# Corn3.net
KiCad netlist of a schematic drawn in EAGLE
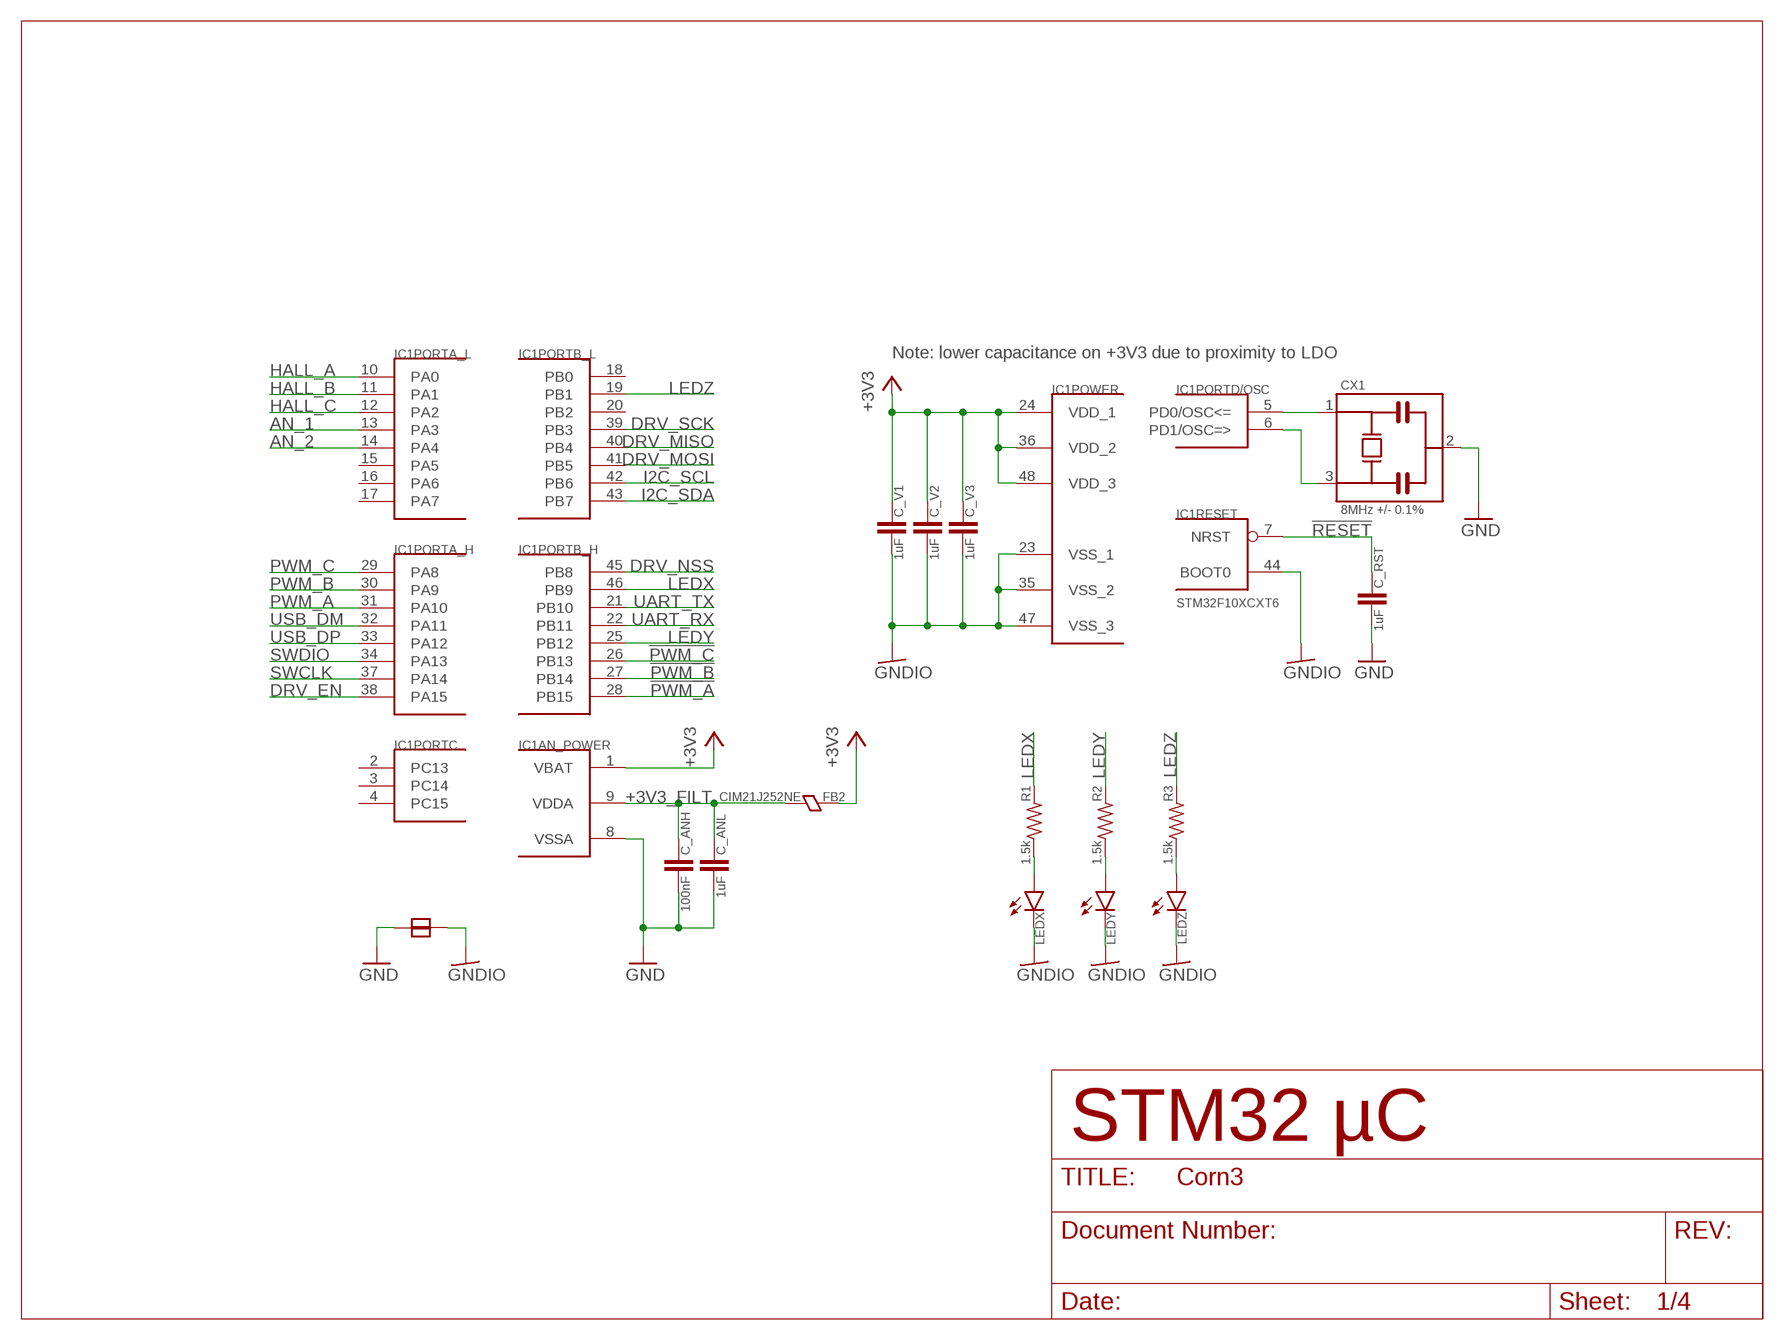
[diagram p0: schematic, sheet 1]
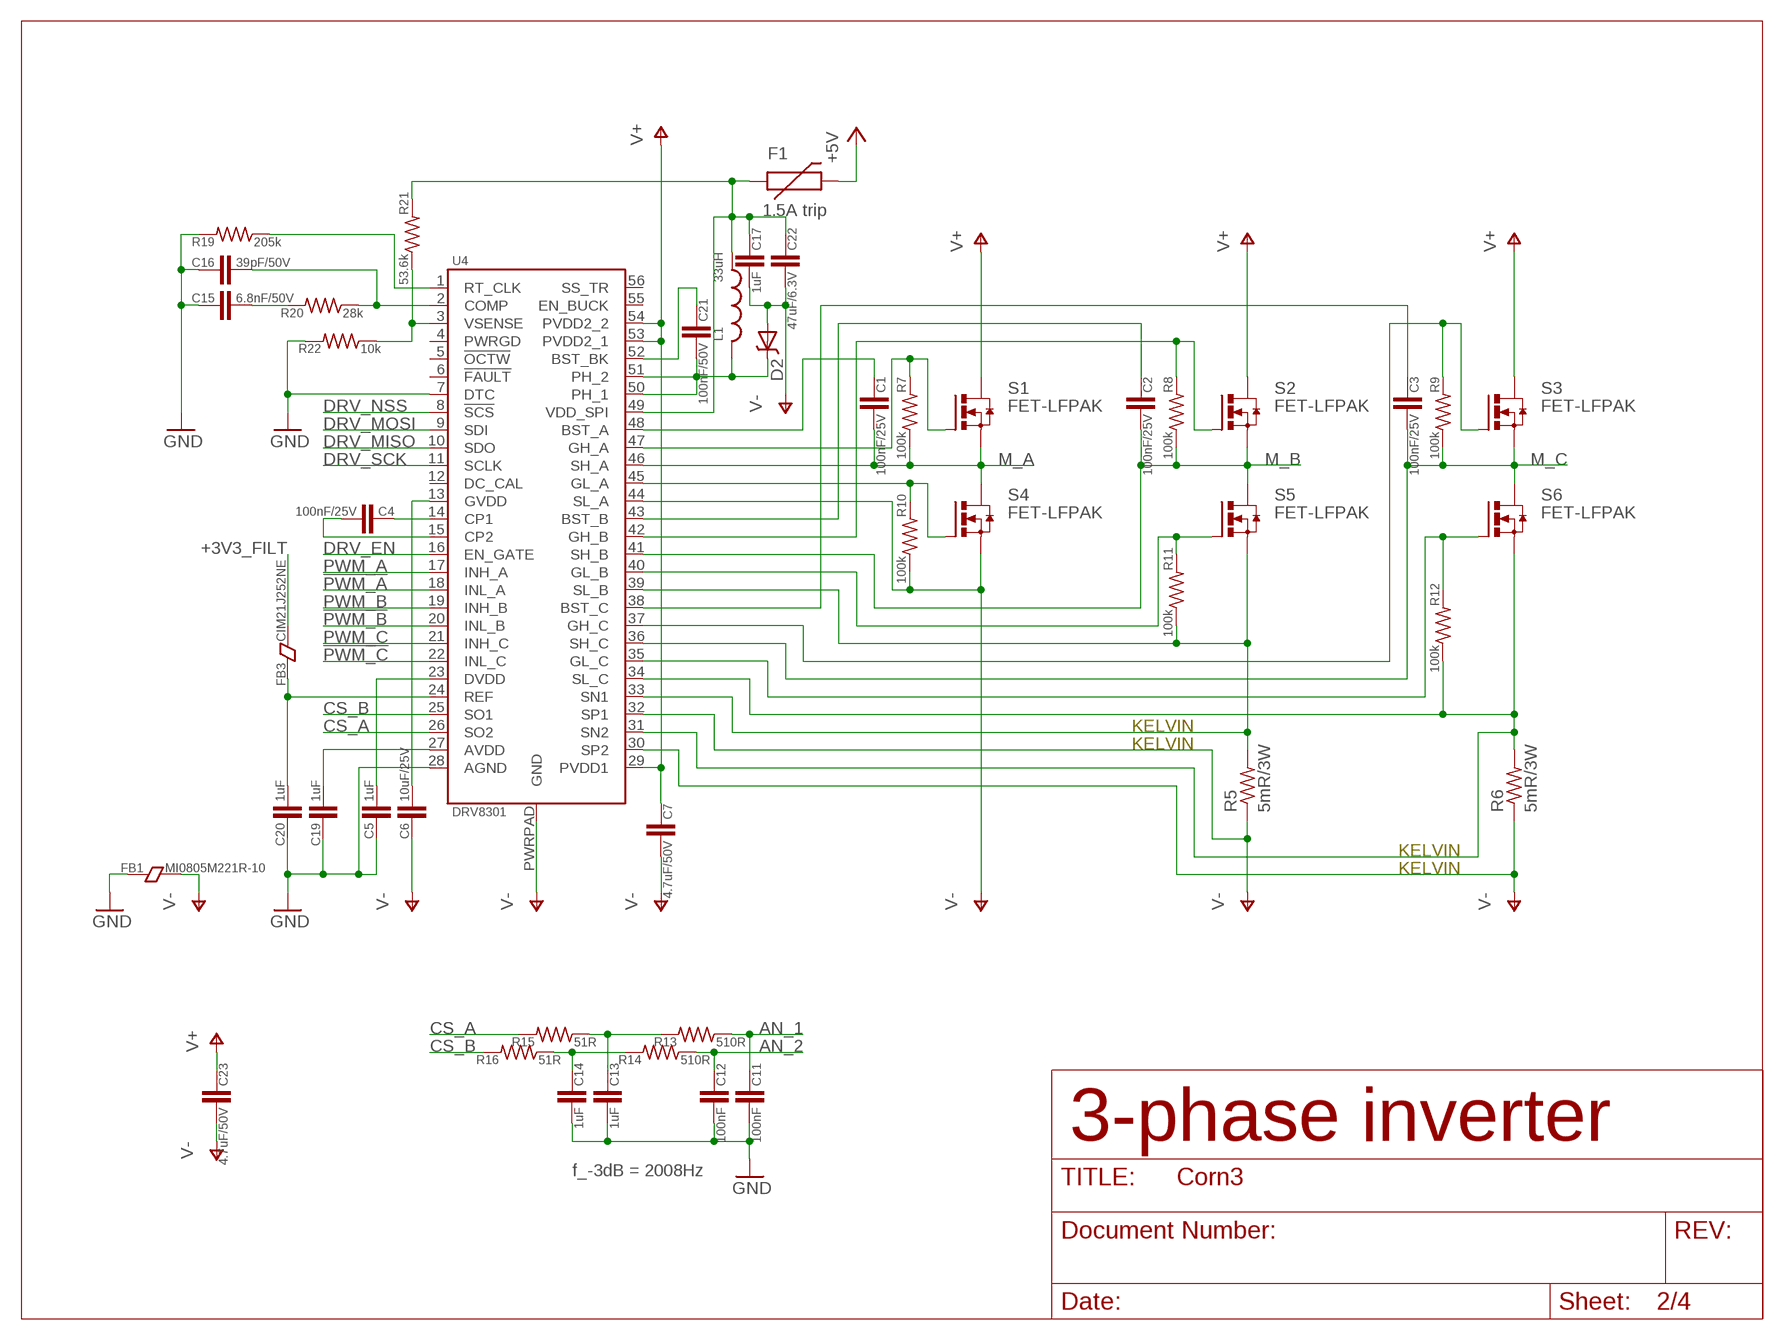
[diagram p1: schematic, sheet 2]
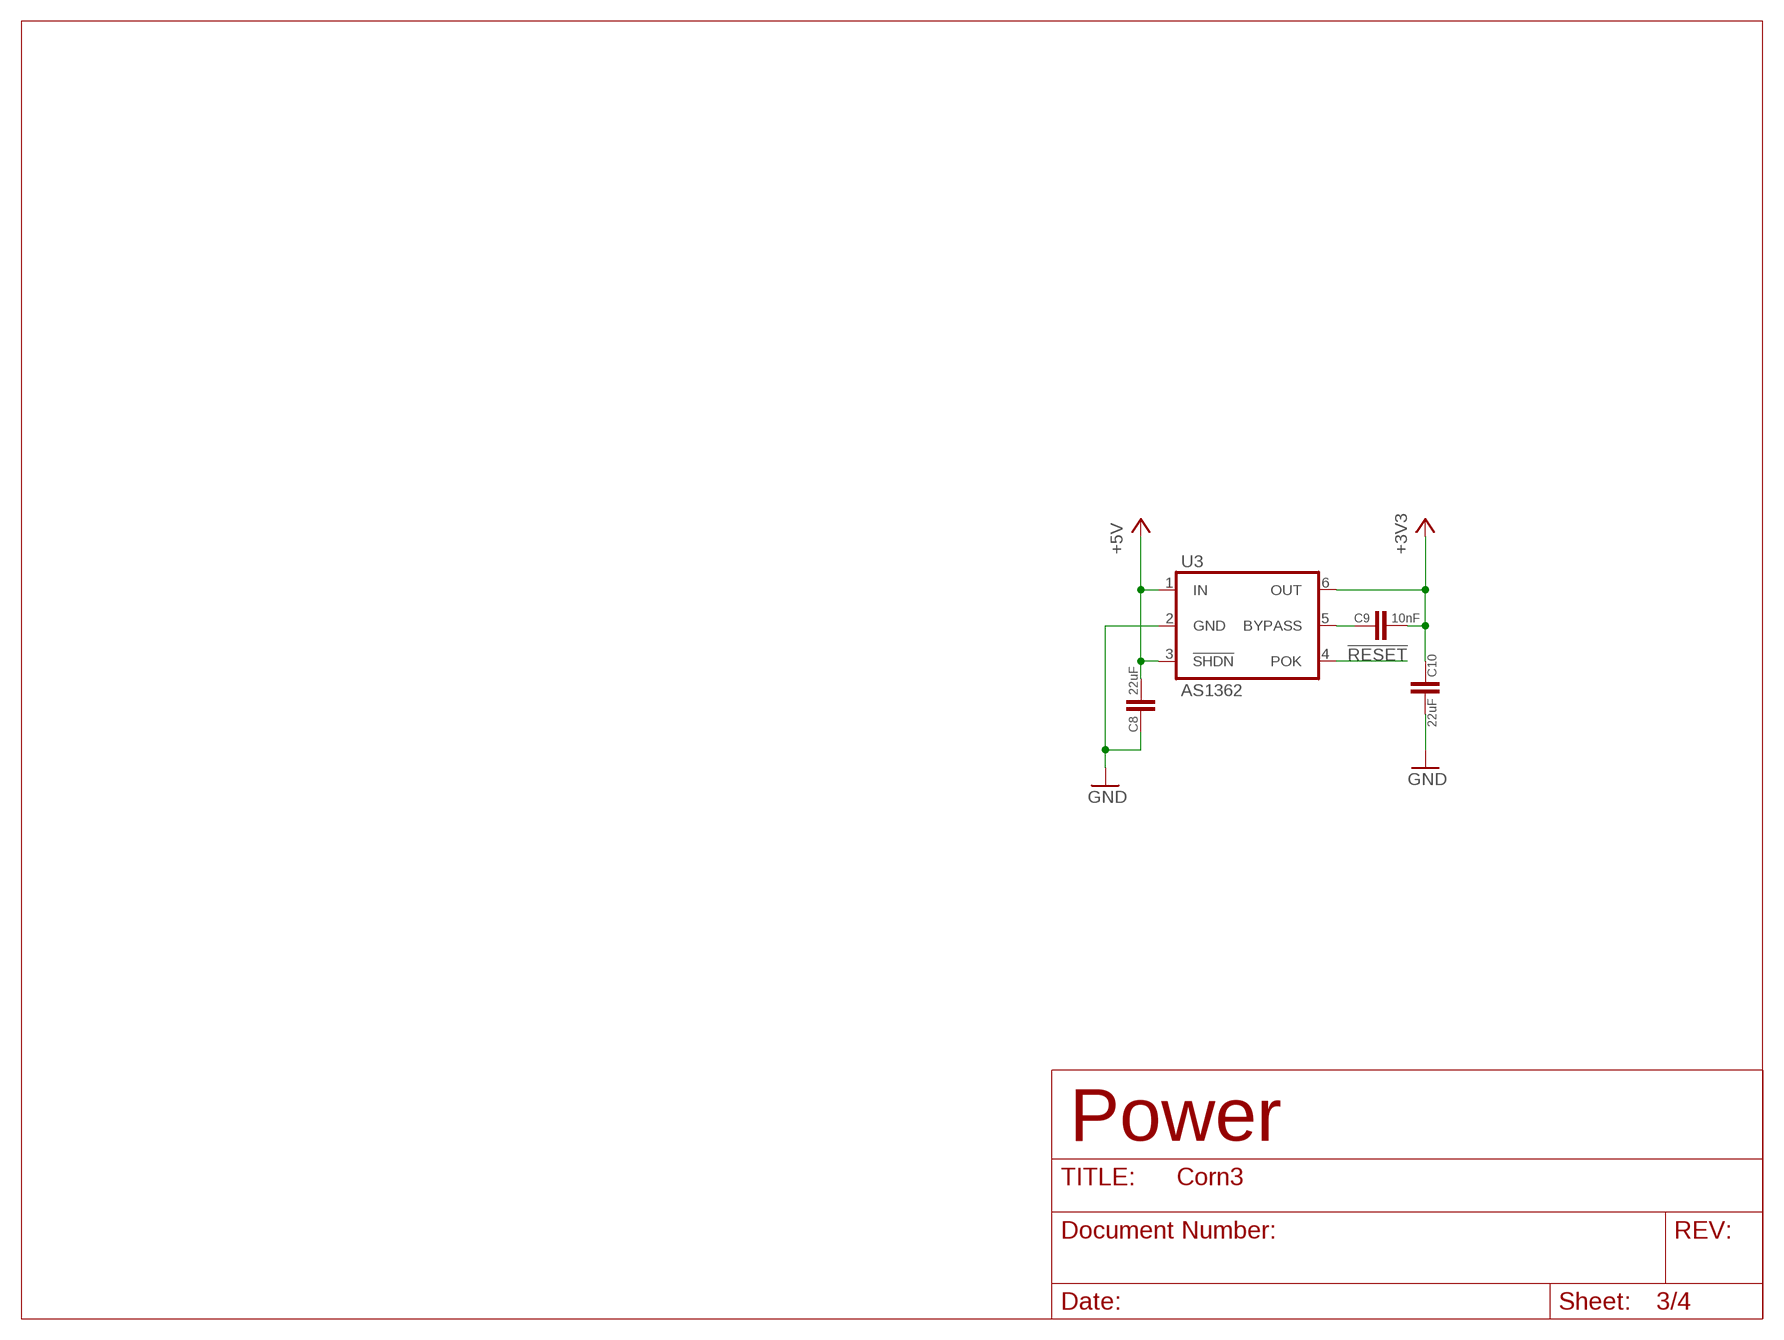
[diagram p2: schematic, sheet 3]
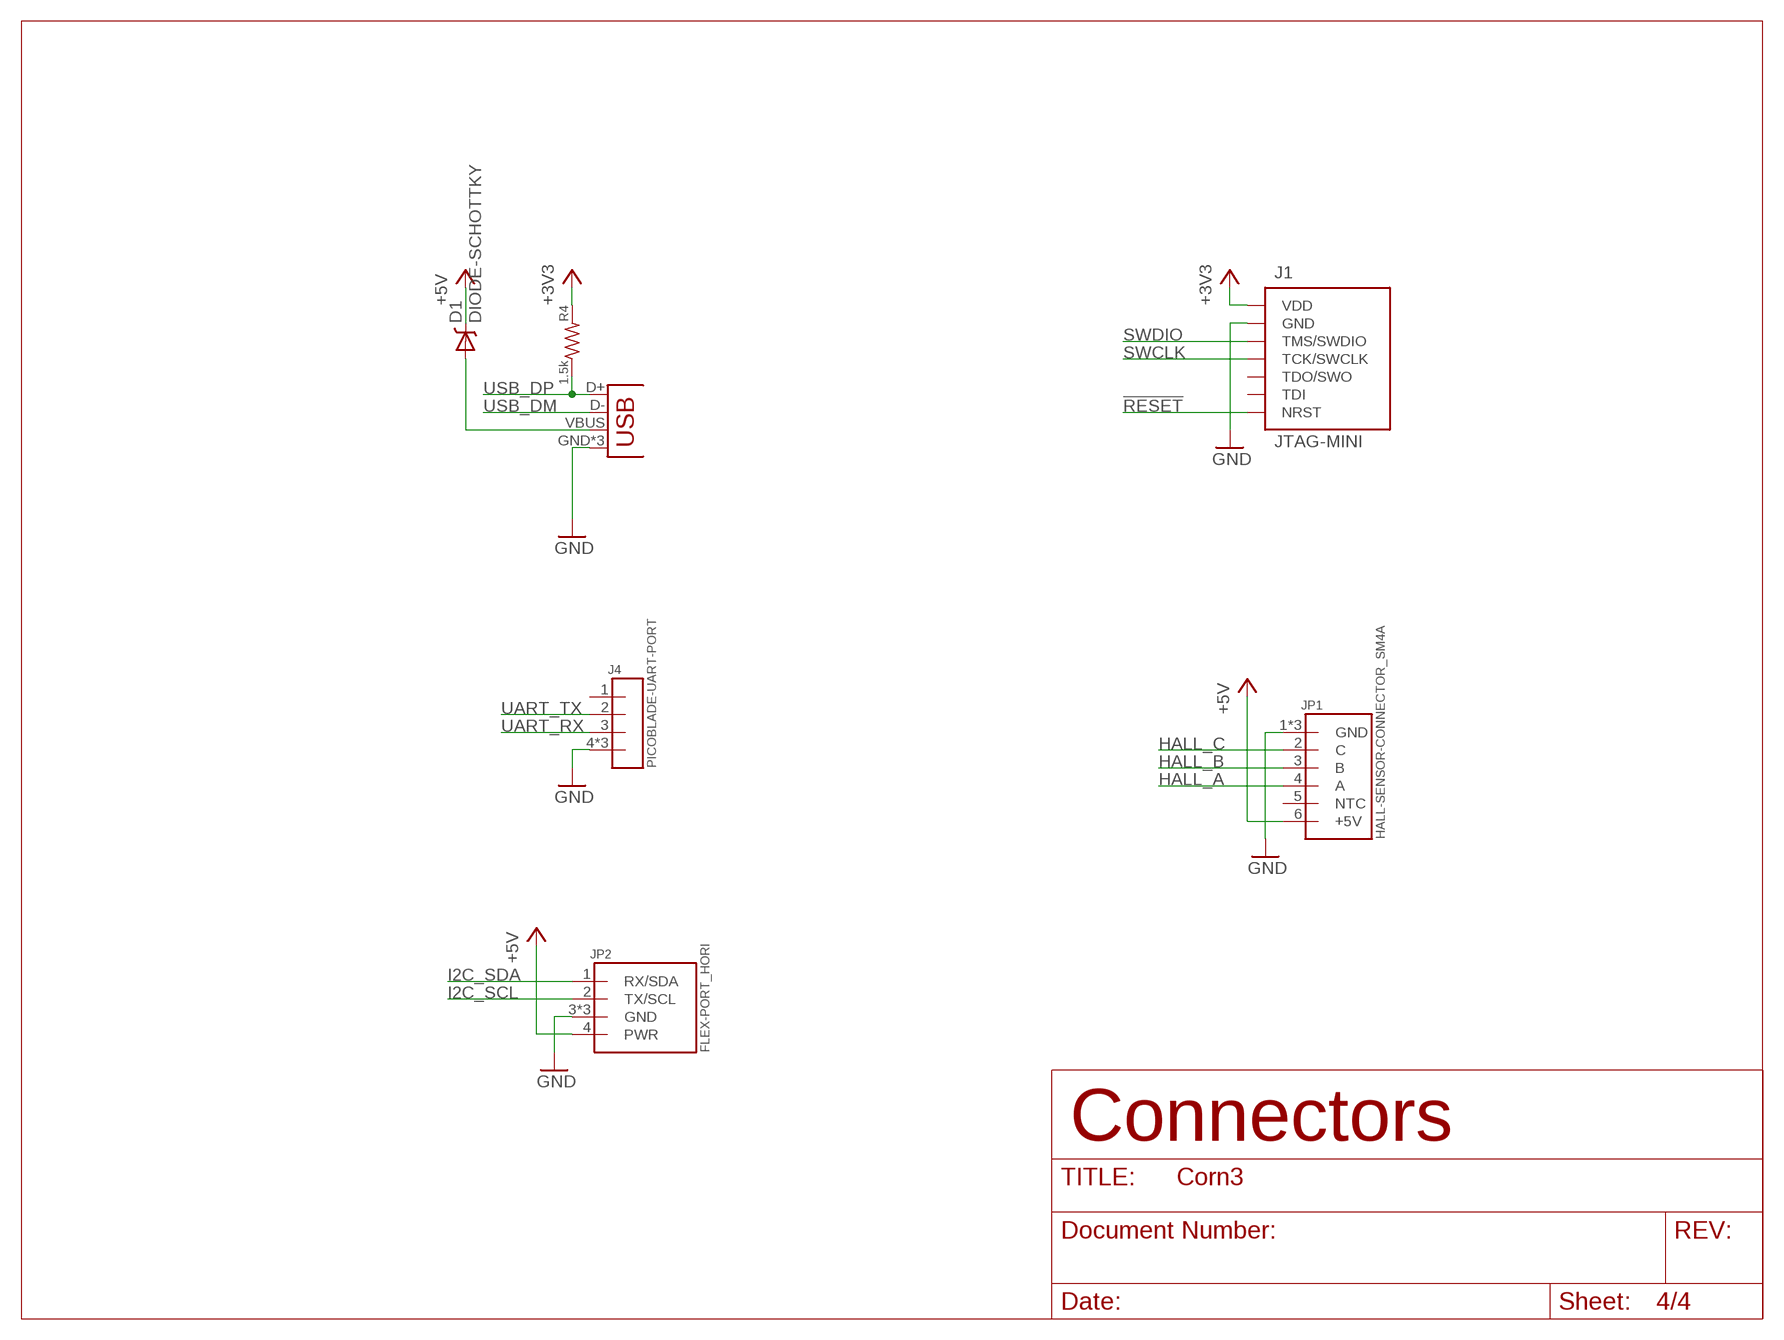
[diagram p3: schematic, sheet 4]

(export (version "E")
  (design (tool "Eeschema 10.0.6"))
  (components
    (comp (ref "C1")
      (value "100nF/25V")
      (footprint "eagle-import:0603")
      (libsource (lib "eagle-import") (part "C0603"))
    )
    (comp (ref "C2")
      (value "100nF/25V")
      (footprint "eagle-import:0603")
      (libsource (lib "eagle-import") (part "C0603"))
    )
    (comp (ref "C3")
      (value "100nF/25V")
      (footprint "eagle-import:0603")
      (libsource (lib "eagle-import") (part "C0603"))
    )
    (comp (ref "C4")
      (value "100nF/25V")
      (footprint "eagle-import:0603")
      (libsource (lib "eagle-import") (part "C0603"))
    )
    (comp (ref "C5")
      (value "1uF")
      (footprint "eagle-import:0603")
      (libsource (lib "eagle-import") (part "C0603"))
    )
    (comp (ref "C6")
      (value "10uF/25V")
      (footprint "eagle-import:0805")
      (libsource (lib "eagle-import") (part "C0805"))
    )
    (comp (ref "C7")
      (value "4.7uF/50V")
      (footprint "eagle-import:1206")
      (libsource (lib "eagle-import") (part "C1206"))
    )
    (comp (ref "C11")
      (value "100nF")
      (footprint "eagle-import:0603")
      (libsource (lib "eagle-import") (part "C0603"))
    )
    (comp (ref "C12")
      (value "100nF")
      (footprint "eagle-import:0603")
      (libsource (lib "eagle-import") (part "C0603"))
    )
    (comp (ref "C13")
      (value "1uF")
      (footprint "eagle-import:0603")
      (libsource (lib "eagle-import") (part "C0603"))
    )
    (comp (ref "C14")
      (value "1uF")
      (footprint "eagle-import:0603")
      (libsource (lib "eagle-import") (part "C0603"))
    )
    (comp (ref "C15")
      (value "6.8nF/50V")
      (footprint "eagle-import:0603")
      (libsource (lib "eagle-import") (part "C0603"))
    )
    (comp (ref "C16")
      (value "39pF/50V")
      (footprint "eagle-import:0603")
      (libsource (lib "eagle-import") (part "C0603"))
    )
    (comp (ref "C17")
      (value "1uF")
      (footprint "eagle-import:0603")
      (libsource (lib "eagle-import") (part "C0603"))
    )
    (comp (ref "C19")
      (value "1uF")
      (footprint "eagle-import:0603")
      (libsource (lib "eagle-import") (part "C0603"))
    )
    (comp (ref "C20")
      (value "1uF")
      (footprint "eagle-import:0603")
      (libsource (lib "eagle-import") (part "C0603"))
    )
    (comp (ref "C21")
      (value "100nF/50V")
      (footprint "eagle-import:0603")
      (libsource (lib "eagle-import") (part "C0603"))
    )
    (comp (ref "C22")
      (value "47uF/6.3V")
      (footprint "eagle-import:0805")
      (libsource (lib "eagle-import") (part "C0805"))
    )
    (comp (ref "C23")
      (value "4.7uF/50V")
      (footprint "eagle-import:1206")
      (libsource (lib "eagle-import") (part "C1206"))
    )
    (comp (ref "D2")
      (value "DIODE-SCHOTTKY_")
      (footprint "eagle-import:SMA-DIODE")
      (libsource (lib "eagle-import") (part "DIODE-SCHOTTKY_"))
    )
    (comp (ref "F1")
      (value "1.5A trip")
      (footprint "eagle-import:PTC-1206")
      (libsource (lib "eagle-import") (part "PTCSMD"))
    )
    (comp (ref "FB1")
      (value "MI0805M221R-10")
      (footprint "eagle-import:0805")
      (libsource (lib "eagle-import") (part "FERRITE0805"))
    )
    (comp (ref "FB3")
      (value "CIM21J252NE")
      (footprint "eagle-import:0805")
      (libsource (lib "eagle-import") (part "FERRITE0805"))
    )
    (comp (ref "L1")
      (value "33uH")
      (footprint "eagle-import:TAIYO-YUDEN_NR40")
      (libsource (lib "eagle-import") (part "L-US_NR40"))
    )
    (comp (ref "R5")
      (value "5mR/3W")
      (footprint "eagle-import:R2512")
      (libsource (lib "eagle-import") (part "R-US_R2512"))
    )
    (comp (ref "R6")
      (value "5mR/3W")
      (footprint "eagle-import:R2512")
      (libsource (lib "eagle-import") (part "R-US_R2512"))
    )
    (comp (ref "R7")
      (value "100k")
      (footprint "eagle-import:0603")
      (libsource (lib "eagle-import") (part "R0603"))
    )
    (comp (ref "R8")
      (value "100k")
      (footprint "eagle-import:0603")
      (libsource (lib "eagle-import") (part "R0603"))
    )
    (comp (ref "R9")
      (value "100k")
      (footprint "eagle-import:0603")
      (libsource (lib "eagle-import") (part "R0603"))
    )
    (comp (ref "R10")
      (value "100k")
      (footprint "eagle-import:0603")
      (libsource (lib "eagle-import") (part "R0603"))
    )
    (comp (ref "R11")
      (value "100k")
      (footprint "eagle-import:0603")
      (libsource (lib "eagle-import") (part "R0603"))
    )
    (comp (ref "R12")
      (value "100k")
      (footprint "eagle-import:0603")
      (libsource (lib "eagle-import") (part "R0603"))
    )
    (comp (ref "R13")
      (value "510R")
      (footprint "eagle-import:0603")
      (libsource (lib "eagle-import") (part "R0603"))
    )
    (comp (ref "R14")
      (value "510R")
      (footprint "eagle-import:0603")
      (libsource (lib "eagle-import") (part "R0603"))
    )
    (comp (ref "R15")
      (value "51R")
      (footprint "eagle-import:0603")
      (libsource (lib "eagle-import") (part "R0603"))
    )
    (comp (ref "R16")
      (value "51R")
      (footprint "eagle-import:0603")
      (libsource (lib "eagle-import") (part "R0603"))
    )
    (comp (ref "R19")
      (value "205k")
      (footprint "eagle-import:0603")
      (libsource (lib "eagle-import") (part "R0603"))
    )
    (comp (ref "R20")
      (value "28k")
      (footprint "eagle-import:0603")
      (libsource (lib "eagle-import") (part "R0603"))
    )
    (comp (ref "R21")
      (value "53.6k")
      (footprint "eagle-import:0603")
      (libsource (lib "eagle-import") (part "R0603"))
    )
    (comp (ref "R22")
      (value "10k")
      (footprint "eagle-import:0603")
      (libsource (lib "eagle-import") (part "R0603"))
    )
    (comp (ref "S1")
      (value "FET-LFPAK")
      (footprint "eagle-import:SON-5X6")
      (libsource (lib "eagle-import") (part "MOSFET-N56"))
    )
    (comp (ref "S2")
      (value "FET-LFPAK")
      (footprint "eagle-import:SON-5X6")
      (libsource (lib "eagle-import") (part "MOSFET-N56"))
    )
    (comp (ref "S3")
      (value "FET-LFPAK")
      (footprint "eagle-import:SON-5X6")
      (libsource (lib "eagle-import") (part "MOSFET-N56"))
    )
    (comp (ref "S4")
      (value "FET-LFPAK")
      (footprint "eagle-import:SON-5X6")
      (libsource (lib "eagle-import") (part "MOSFET-N56"))
    )
    (comp (ref "S5")
      (value "FET-LFPAK")
      (footprint "eagle-import:SON-5X6")
      (libsource (lib "eagle-import") (part "MOSFET-N56"))
    )
    (comp (ref "S6")
      (value "FET-LFPAK")
      (footprint "eagle-import:SON-5X6")
      (libsource (lib "eagle-import") (part "MOSFET-N56"))
    )
    (comp (ref "U4")
      (value "DRV8301")
      (footprint "eagle-import:HTSSOP-56")
      (libsource (lib "eagle-import") (part "DRV8301"))
    )
    (comp (ref "C8")
      (value "22uF")
      (footprint "eagle-import:0805")
      (libsource (lib "eagle-import") (part "C0805"))
    )
    (comp (ref "C9")
      (value "10nF")
      (footprint "eagle-import:0603")
      (libsource (lib "eagle-import") (part "C0603"))
    )
    (comp (ref "C10")
      (value "22uF")
      (footprint "eagle-import:0805")
      (libsource (lib "eagle-import") (part "C0805"))
    )
    (comp (ref "U3")
      (value "AS1362")
      (footprint "eagle-import:SOT23-6")
      (libsource (lib "eagle-import") (part "AS1362"))
    )
    (comp (ref "D1")
      (value "DIODE-SCHOTTKY")
      (footprint "eagle-import:SOD-523")
      (libsource (lib "eagle-import") (part "DIODE-SCHOTTKY"))
    )
    (comp (ref "J1")
      (value "JTAG-MINI")
      (footprint "eagle-import:JTAG-MINI")
      (libsource (lib "eagle-import") (part "JTAG-MINI"))
    )
    (comp (ref "J4")
      (value "PICOBLADE-UART-PORT")
      (footprint "eagle-import:PICOBLADE-04-SMD-RA")
      (libsource (lib "eagle-import") (part "PICOBLADE-UART-PORT"))
    )
    (comp (ref "JP1")
      (value "HALL-SENSOR-CONNECTOR_SM4A")
      (footprint "eagle-import:JST_S6B-ZR-SM4A")
      (libsource (lib "eagle-import") (part "HALL-SENSOR-CONNECTOR_SM4A"))
    )
    (comp (ref "JP2")
      (value "FLEX-PORT_HORI")
      (footprint "eagle-import:JST_SM04B-SRSS")
      (libsource (lib "eagle-import") (part "FLEX-PORT_HORI"))
    )
    (comp (ref "JP3")
      (value "USB-MICROB")
      (footprint "eagle-import:USB-MICROB")
      (libsource (lib "eagle-import") (part "USB-MICROB"))
    )
    (comp (ref "R4")
      (value "1.5k")
      (footprint "eagle-import:0603")
      (libsource (lib "eagle-import") (part "R0603"))
    )
    (comp (ref "CX1")
      (value "8MHz +/- 0.1%")
      (footprint "eagle-import:MURATA_CSTCE")
      (libsource (lib "eagle-import") (part "MURATA_CSTCE"))
    )
    (comp (ref "C_ANH")
      (value "100nF")
      (footprint "eagle-import:0603")
      (libsource (lib "eagle-import") (part "C0603"))
    )
    (comp (ref "C_ANL")
      (value "1uF")
      (footprint "eagle-import:0603")
      (libsource (lib "eagle-import") (part "C0603"))
    )
    (comp (ref "C_RST")
      (value "1uF")
      (footprint "eagle-import:0603")
      (libsource (lib "eagle-import") (part "C0603"))
    )
    (comp (ref "C_V1")
      (value "1uF")
      (footprint "eagle-import:0603")
      (libsource (lib "eagle-import") (part "C0603"))
    )
    (comp (ref "C_V2")
      (value "1uF")
      (footprint "eagle-import:0603")
      (libsource (lib "eagle-import") (part "C0603"))
    )
    (comp (ref "C_V3")
      (value "1uF")
      (footprint "eagle-import:0603")
      (libsource (lib "eagle-import") (part "C0603"))
    )
    (comp (ref "FB2")
      (value "CIM21J252NE")
      (footprint "eagle-import:0805")
      (libsource (lib "eagle-import") (part "FERRITE0805"))
    )
    (comp (ref "IC1")
      (value "STM32F10XCXT6")
      (footprint "eagle-import:TQFP48")
      (libsource (lib "eagle-import") (part "STM32F10XCXT6"))
    )
    (comp (ref "JUMPER-GND-GNDIO")
      (value "JUMPER5025")
      (footprint "eagle-import:5025")
      (libsource (lib "eagle-import") (part "JUMPER5025"))
    )
    (comp (ref "LEDX")
      (value "LED0805")
      (footprint "eagle-import:0805_POL")
      (libsource (lib "eagle-import") (part "LED0805"))
    )
    (comp (ref "LEDY")
      (value "LED0805")
      (footprint "eagle-import:0805_POL")
      (libsource (lib "eagle-import") (part "LED0805"))
    )
    (comp (ref "LEDZ")
      (value "LED0805")
      (footprint "eagle-import:0805_POL")
      (libsource (lib "eagle-import") (part "LED0805"))
    )
    (comp (ref "R1")
      (value "1.5k")
      (footprint "eagle-import:0603")
      (libsource (lib "eagle-import") (part "R0603"))
    )
    (comp (ref "R2")
      (value "1.5k")
      (footprint "eagle-import:0603")
      (libsource (lib "eagle-import") (part "R0603"))
    )
    (comp (ref "R3")
      (value "1.5k")
      (footprint "eagle-import:0603")
      (libsource (lib "eagle-import") (part "R0603"))
    )
  )
  (nets
    (net (code "1") (name "+3V3") (class "Default")
      (node (ref "C10") (pin "1") (pinfunction "1_1") (pintype "passive"))
      (node (ref "C9") (pin "2") (pinfunction "2_2") (pintype "passive"))
      (node (ref "C_V1") (pin "1") (pinfunction "1_1") (pintype "passive"))
      (node (ref "C_V2") (pin "1") (pinfunction "1_1") (pintype "passive"))
      (node (ref "C_V3") (pin "1") (pinfunction "1_1") (pintype "passive"))
      (node (ref "FB2") (pin "2") (pinfunction "2_2") (pintype "passive"))
      (node (ref "IC1") (pin "1") (pinfunction "VBAT_1") (pintype "power_in"))
      (node (ref "IC1") (pin "24") (pinfunction "VDD_1_24") (pintype "power_in"))
      (node (ref "IC1") (pin "36") (pinfunction "VDD_2_36") (pintype "power_in"))
      (node (ref "IC1") (pin "48") (pinfunction "VDD_3_48") (pintype "power_in"))
      (node (ref "J1") (pin "VDD") (pinfunction "VDD_VDD") (pintype "bidirectional"))
      (node (ref "R4") (pin "2") (pinfunction "2_2") (pintype "passive"))
      (node (ref "U3") (pin "6") (pinfunction "OUT_6") (pintype "power_in"))
    )
    (net (code "2") (name "+3V3_FILT") (class "Default")
      (node (ref "C_ANH") (pin "1") (pinfunction "1_1") (pintype "passive"))
      (node (ref "C_ANL") (pin "1") (pinfunction "1_1") (pintype "passive"))
      (node (ref "FB2") (pin "1") (pinfunction "1_1") (pintype "passive"))
      (node (ref "FB3") (pin "1") (pinfunction "1_1") (pintype "passive"))
      (node (ref "IC1") (pin "9") (pinfunction "VDDA_9") (pintype "power_in"))
    )
    (net (code "3") (name "+5V") (class "Default")
      (node (ref "C8") (pin "2") (pinfunction "2_2") (pintype "passive"))
      (node (ref "D1") (pin "C") (pinfunction "C_C") (pintype "passive"))
      (node (ref "F1") (pin "2") (pinfunction "2_2") (pintype "bidirectional"))
      (node (ref "JP1") (pin "6") (pinfunction "+5V_6") (pintype "bidirectional"))
      (node (ref "JP2") (pin "4") (pinfunction "PWR_4") (pintype "bidirectional"))
      (node (ref "U3") (pin "1") (pinfunction "IN_1") (pintype "power_in"))
      (node (ref "U3") (pin "3") (pinfunction "~{SHDN}_3") (pintype "input"))
    )
    (net (code "4") (name "AN_1") (class "Default")
      (node (ref "C11") (pin "1") (pinfunction "1_1") (pintype "passive"))
      (node (ref "IC1") (pin "13") (pinfunction "PA3_13") (pintype "bidirectional"))
      (node (ref "R13") (pin "1") (pinfunction "1_1") (pintype "passive"))
    )
    (net (code "5") (name "AN_2") (class "Default")
      (node (ref "C12") (pin "1") (pinfunction "1_1") (pintype "passive"))
      (node (ref "IC1") (pin "14") (pinfunction "PA4_14") (pintype "bidirectional"))
      (node (ref "R14") (pin "1") (pinfunction "1_1") (pintype "passive"))
    )
    (net (code "6") (name "CS_A") (class "Default")
      (node (ref "R15") (pin "2") (pinfunction "2_2") (pintype "passive"))
      (node (ref "U4") (pin "26") (pinfunction "SO2_26") (pintype "output"))
    )
    (net (code "7") (name "CS_B") (class "Default")
      (node (ref "R16") (pin "2") (pinfunction "2_2") (pintype "passive"))
      (node (ref "U4") (pin "25") (pinfunction "SO1_25") (pintype "output"))
    )
    (net (code "8") (name "DRV_EN") (class "Default")
      (node (ref "IC1") (pin "38") (pinfunction "PA15_38") (pintype "bidirectional"))
      (node (ref "U4") (pin "16") (pinfunction "EN_GATE_16") (pintype "input"))
    )
    (net (code "9") (name "DRV_MISO") (class "Default")
      (node (ref "IC1") (pin "40") (pinfunction "PB4_40") (pintype "bidirectional"))
      (node (ref "U4") (pin "10") (pinfunction "SDO_10") (pintype "output"))
    )
    (net (code "10") (name "DRV_MOSI") (class "Default")
      (node (ref "IC1") (pin "41") (pinfunction "PB5_41") (pintype "bidirectional"))
      (node (ref "U4") (pin "9") (pinfunction "SDI_9") (pintype "input"))
    )
    (net (code "11") (name "DRV_NSS") (class "Default")
      (node (ref "IC1") (pin "45") (pinfunction "PB8_45") (pintype "bidirectional"))
      (node (ref "U4") (pin "8") (pinfunction "~{SCS}_8") (pintype "input"))
    )
    (net (code "12") (name "DRV_SCK") (class "Default")
      (node (ref "IC1") (pin "39") (pinfunction "PB3_39") (pintype "bidirectional"))
      (node (ref "U4") (pin "11") (pinfunction "SCLK_11") (pintype "input"))
    )
    (net (code "13") (name "GND") (class "Default")
      (node (ref "C10") (pin "2") (pinfunction "2_2") (pintype "passive"))
      (node (ref "C11") (pin "2") (pinfunction "2_2") (pintype "passive"))
      (node (ref "C12") (pin "2") (pinfunction "2_2") (pintype "passive"))
      (node (ref "C13") (pin "2") (pinfunction "2_2") (pintype "passive"))
      (node (ref "C14") (pin "2") (pinfunction "2_2") (pintype "passive"))
      (node (ref "C15") (pin "1") (pinfunction "1_1") (pintype "passive"))
      (node (ref "C16") (pin "1") (pinfunction "1_1") (pintype "passive"))
      (node (ref "C19") (pin "1") (pinfunction "1_1") (pintype "passive"))
      (node (ref "C20") (pin "1") (pinfunction "1_1") (pintype "passive"))
      (node (ref "C5") (pin "1") (pinfunction "1_1") (pintype "passive"))
      (node (ref "C8") (pin "1") (pinfunction "1_1") (pintype "passive"))
      (node (ref "CX1") (pin "2") (pinfunction "P$2_2") (pintype "bidirectional"))
      (node (ref "C_ANH") (pin "2") (pinfunction "2_2") (pintype "passive"))
      (node (ref "C_ANL") (pin "2") (pinfunction "2_2") (pintype "passive"))
      (node (ref "C_RST") (pin "2") (pinfunction "2_2") (pintype "passive"))
      (node (ref "FB1") (pin "2") (pinfunction "2_2") (pintype "passive"))
      (node (ref "IC1") (pin "8") (pinfunction "VSSA_8") (pintype "power_in"))
      (node (ref "J1") (pin "GND1") (pinfunction "GND_GND1") (pintype "bidirectional"))
      (node (ref "J1") (pin "GND2") (pinfunction "GND_GND2") (pintype "bidirectional"))
      (node (ref "J1") (pin "GND3") (pinfunction "GND_GND3") (pintype "bidirectional"))
      (node (ref "J1") (pin "GND4") (pinfunction "GND_GND4") (pintype "bidirectional"))
      (node (ref "J4") (pin "4") (pinfunction "4_4") (pintype "bidirectional"))
      (node (ref "J4") (pin "TAB1") (pinfunction "4_TAB1") (pintype "bidirectional"))
      (node (ref "J4") (pin "TAB2") (pinfunction "4_TAB2") (pintype "bidirectional"))
      (node (ref "JP1") (pin "1") (pinfunction "GND_1") (pintype "bidirectional"))
      (node (ref "JP1") (pin "TAB1") (pinfunction "GND_TAB1") (pintype "bidirectional"))
      (node (ref "JP1") (pin "TAB2") (pinfunction "GND_TAB2") (pintype "bidirectional"))
      (node (ref "JP2") (pin "3") (pinfunction "GND_3") (pintype "bidirectional"))
      (node (ref "JP2") (pin "TAB1") (pinfunction "GND_TAB1") (pintype "bidirectional"))
      (node (ref "JP2") (pin "TAB2") (pinfunction "GND_TAB2") (pintype "bidirectional"))
      (node (ref "JP3") (pin "GND") (pinfunction "GND_GND") (pintype "bidirectional"))
      (node (ref "JP3") (pin "MT1") (pinfunction "GND_MT1") (pintype "bidirectional"))
      (node (ref "JP3") (pin "MT2") (pinfunction "GND_MT2") (pintype "bidirectional"))
      (node (ref "JUMPER-GND-GNDIO") (pin "1") (pinfunction "1_1") (pintype "bidirectional"))
      (node (ref "R19") (pin "2") (pinfunction "2_2") (pintype "passive"))
      (node (ref "R22") (pin "2") (pinfunction "2_2") (pintype "passive"))
      (node (ref "U3") (pin "2") (pinfunction "GND_2") (pintype "power_in"))
      (node (ref "U4") (pin "28") (pinfunction "AGND_28") (pintype "power_in"))
      (node (ref "U4") (pin "7") (pinfunction "DTC_7") (pintype "input"))
    )
    (net (code "14") (name "GNDIO") (class "Default")
      (node (ref "C_V1") (pin "2") (pinfunction "2_2") (pintype "passive"))
      (node (ref "C_V2") (pin "2") (pinfunction "2_2") (pintype "passive"))
      (node (ref "C_V3") (pin "2") (pinfunction "2_2") (pintype "passive"))
      (node (ref "IC1") (pin "23") (pinfunction "VSS_1_23") (pintype "power_in"))
      (node (ref "IC1") (pin "35") (pinfunction "VSS_2_35") (pintype "power_in"))
      (node (ref "IC1") (pin "44") (pinfunction "BOOT0_44") (pintype "input"))
      (node (ref "IC1") (pin "47") (pinfunction "VSS_3_47") (pintype "power_in"))
      (node (ref "JUMPER-GND-GNDIO") (pin "2") (pinfunction "2_2") (pintype "bidirectional"))
      (node (ref "LEDX") (pin "-") (pinfunction "C_-") (pintype "passive"))
      (node (ref "LEDY") (pin "-") (pinfunction "C_-") (pintype "passive"))
      (node (ref "LEDZ") (pin "-") (pinfunction "C_-") (pintype "passive"))
    )
    (net (code "15") (name "HALL_A") (class "Default")
      (node (ref "IC1") (pin "10") (pinfunction "PA0_10") (pintype "bidirectional"))
      (node (ref "JP1") (pin "4") (pinfunction "A_4") (pintype "bidirectional"))
    )
    (net (code "16") (name "HALL_B") (class "Default")
      (node (ref "IC1") (pin "11") (pinfunction "PA1_11") (pintype "bidirectional"))
      (node (ref "JP1") (pin "3") (pinfunction "B_3") (pintype "bidirectional"))
    )
    (net (code "17") (name "HALL_C") (class "Default")
      (node (ref "IC1") (pin "12") (pinfunction "PA2_12") (pintype "bidirectional"))
      (node (ref "JP1") (pin "2") (pinfunction "C_2") (pintype "bidirectional"))
    )
    (net (code "18") (name "I2C_SCL") (class "Default")
      (node (ref "IC1") (pin "42") (pinfunction "PB6_42") (pintype "bidirectional"))
      (node (ref "JP2") (pin "2") (pinfunction "TX/SCL_2") (pintype "bidirectional"))
    )
    (net (code "19") (name "I2C_SDA") (class "Default")
      (node (ref "IC1") (pin "43") (pinfunction "PB7_43") (pintype "bidirectional"))
      (node (ref "JP2") (pin "1") (pinfunction "RX/SDA_1") (pintype "bidirectional"))
    )
    (net (code "20") (name "LEDX") (class "Default")
      (node (ref "IC1") (pin "46") (pinfunction "PB9_46") (pintype "bidirectional"))
      (node (ref "R1") (pin "2") (pinfunction "2_2") (pintype "passive"))
    )
    (net (code "21") (name "LEDY") (class "Default")
      (node (ref "IC1") (pin "25") (pinfunction "PB12_25") (pintype "bidirectional"))
      (node (ref "R2") (pin "2") (pinfunction "2_2") (pintype "passive"))
    )
    (net (code "22") (name "LEDZ") (class "Default")
      (node (ref "IC1") (pin "19") (pinfunction "PB1_19") (pintype "bidirectional"))
      (node (ref "R3") (pin "2") (pinfunction "2_2") (pintype "passive"))
    )
    (net (code "23") (name "M_A") (class "Default")
      (node (ref "C1") (pin "2") (pinfunction "2_2") (pintype "passive"))
      (node (ref "R7") (pin "1") (pinfunction "1_1") (pintype "passive"))
      (node (ref "S1") (pin "S1") (pinfunction "S_S1") (pintype "passive"))
      (node (ref "S1") (pin "S2") (pinfunction "S_S2") (pintype "passive"))
      (node (ref "S1") (pin "S3") (pinfunction "S_S3") (pintype "passive"))
      (node (ref "S4") (pin "D") (pinfunction "D_D") (pintype "passive"))
      (node (ref "S4") (pin "D_") (pinfunction "D_D_") (pintype "passive"))
      (node (ref "U4") (pin "46") (pinfunction "SH_A_46") (pintype "bidirectional"))
    )
    (net (code "24") (name "M_B") (class "Default")
      (node (ref "C2") (pin "2") (pinfunction "2_2") (pintype "passive"))
      (node (ref "R8") (pin "1") (pinfunction "1_1") (pintype "passive"))
      (node (ref "S2") (pin "S1") (pinfunction "S_S1") (pintype "passive"))
      (node (ref "S2") (pin "S2") (pinfunction "S_S2") (pintype "passive"))
      (node (ref "S2") (pin "S3") (pinfunction "S_S3") (pintype "passive"))
      (node (ref "S5") (pin "D") (pinfunction "D_D") (pintype "passive"))
      (node (ref "S5") (pin "D_") (pinfunction "D_D_") (pintype "passive"))
      (node (ref "U4") (pin "41") (pinfunction "SH_B_41") (pintype "bidirectional"))
    )
    (net (code "25") (name "M_C") (class "Default")
      (node (ref "C3") (pin "2") (pinfunction "2_2") (pintype "passive"))
      (node (ref "R9") (pin "1") (pinfunction "1_1") (pintype "passive"))
      (node (ref "S3") (pin "S1") (pinfunction "S_S1") (pintype "passive"))
      (node (ref "S3") (pin "S2") (pinfunction "S_S2") (pintype "passive"))
      (node (ref "S3") (pin "S3") (pinfunction "S_S3") (pintype "passive"))
      (node (ref "S6") (pin "D") (pinfunction "D_D") (pintype "passive"))
      (node (ref "S6") (pin "D_") (pinfunction "D_D_") (pintype "passive"))
      (node (ref "U4") (pin "36") (pinfunction "SH_C_36") (pintype "bidirectional"))
    )
    (net (code "26") (name "Net-(C13-Pad1)") (class "Default")
      (node (ref "C13") (pin "1") (pinfunction "1_1") (pintype "passive"))
      (node (ref "R13") (pin "2") (pinfunction "2_2") (pintype "passive"))
      (node (ref "R15") (pin "1") (pinfunction "1_1") (pintype "passive"))
    )
    (net (code "27") (name "Net-(C14-Pad1)") (class "Default")
      (node (ref "C14") (pin "1") (pinfunction "1_1") (pintype "passive"))
      (node (ref "R14") (pin "2") (pinfunction "2_2") (pintype "passive"))
      (node (ref "R16") (pin "1") (pinfunction "1_1") (pintype "passive"))
    )
    (net (code "28") (name "Net-(C15-Pad2)") (class "Default")
      (node (ref "C15") (pin "2") (pinfunction "2_2") (pintype "passive"))
      (node (ref "R20") (pin "2") (pinfunction "2_2") (pintype "passive"))
    )
    (net (code "29") (name "Net-(CX1-P$1)") (class "Default")
      (node (ref "CX1") (pin "1") (pinfunction "P$1_1") (pintype "bidirectional"))
      (node (ref "IC1") (pin "5") (pinfunction "PD0/OSC<=_5") (pintype "bidirectional"))
    )
    (net (code "30") (name "Net-(CX1-P$3)") (class "Default")
      (node (ref "CX1") (pin "3") (pinfunction "P$3_3") (pintype "bidirectional"))
      (node (ref "IC1") (pin "6") (pinfunction "PD1/OSC=>_6") (pintype "bidirectional"))
    )
    (net (code "31") (name "Net-(D1-PadA)") (class "Default")
      (node (ref "D1") (pin "A") (pinfunction "A_A") (pintype "passive"))
      (node (ref "JP3") (pin "VBUS") (pinfunction "VBUS_VBUS") (pintype "bidirectional"))
    )
    (net (code "32") (name "Net-(LEDX-A)") (class "Default")
      (node (ref "LEDX") (pin "+") (pinfunction "A_+") (pintype "passive"))
      (node (ref "R1") (pin "1") (pinfunction "1_1") (pintype "passive"))
    )
    (net (code "33") (name "Net-(LEDY-A)") (class "Default")
      (node (ref "LEDY") (pin "+") (pinfunction "A_+") (pintype "passive"))
      (node (ref "R2") (pin "1") (pinfunction "1_1") (pintype "passive"))
    )
    (net (code "34") (name "Net-(LEDZ-A)") (class "Default")
      (node (ref "LEDZ") (pin "+") (pinfunction "A_+") (pintype "passive"))
      (node (ref "R3") (pin "1") (pinfunction "1_1") (pintype "passive"))
    )
    (net (code "35") (name "Net-(U3-BYPASS)") (class "Default")
      (node (ref "C9") (pin "1") (pinfunction "1_1") (pintype "passive"))
      (node (ref "U3") (pin "5") (pinfunction "BYPASS_5") (pintype "bidirectional"))
    )
    (net (code "36") (name "Net-(U4-AVDD)") (class "Default")
      (node (ref "C19") (pin "2") (pinfunction "2_2") (pintype "passive"))
      (node (ref "U4") (pin "27") (pinfunction "AVDD_27") (pintype "power_in"))
    )
    (net (code "37") (name "Net-(U4-BST_A)") (class "Default")
      (node (ref "C1") (pin "1") (pinfunction "1_1") (pintype "passive"))
      (node (ref "U4") (pin "48") (pinfunction "BST_A_48") (pintype "bidirectional"))
    )
    (net (code "38") (name "Net-(U4-BST_B)") (class "Default")
      (node (ref "C2") (pin "1") (pinfunction "1_1") (pintype "passive"))
      (node (ref "U4") (pin "43") (pinfunction "BST_B_43") (pintype "bidirectional"))
    )
    (net (code "39") (name "Net-(U4-BST_BK)") (class "Default")
      (node (ref "C21") (pin "1") (pinfunction "1_1") (pintype "passive"))
      (node (ref "U4") (pin "52") (pinfunction "BST_BK_52") (pintype "power_in"))
    )
    (net (code "40") (name "Net-(U4-BST_C)") (class "Default")
      (node (ref "C3") (pin "1") (pinfunction "1_1") (pintype "passive"))
      (node (ref "U4") (pin "38") (pinfunction "BST_C_38") (pintype "bidirectional"))
    )
    (net (code "41") (name "Net-(U4-COMP)") (class "Default")
      (node (ref "C16") (pin "2") (pinfunction "2_2") (pintype "passive"))
      (node (ref "R20") (pin "1") (pinfunction "1_1") (pintype "passive"))
      (node (ref "U4") (pin "2") (pinfunction "COMP_2") (pintype "output"))
    )
    (net (code "42") (name "Net-(U4-CP1)") (class "Default")
      (node (ref "C4") (pin "1") (pinfunction "1_1") (pintype "passive"))
      (node (ref "U4") (pin "14") (pinfunction "CP1_14") (pintype "power_in"))
    )
    (net (code "43") (name "Net-(U4-CP2)") (class "Default")
      (node (ref "C4") (pin "2") (pinfunction "2_2") (pintype "passive"))
      (node (ref "U4") (pin "15") (pinfunction "CP2_15") (pintype "power_in"))
    )
    (net (code "44") (name "Net-(U4-DVDD)") (class "Default")
      (node (ref "C5") (pin "2") (pinfunction "2_2") (pintype "passive"))
      (node (ref "U4") (pin "23") (pinfunction "DVDD_23") (pintype "power_in"))
    )
    (net (code "45") (name "Net-(U4-GH_A)") (class "Default")
      (node (ref "R7") (pin "2") (pinfunction "2_2") (pintype "passive"))
      (node (ref "S1") (pin "G") (pinfunction "G_G") (pintype "passive"))
      (node (ref "U4") (pin "47") (pinfunction "GH_A_47") (pintype "bidirectional"))
    )
    (net (code "46") (name "Net-(U4-GH_B)") (class "Default")
      (node (ref "R8") (pin "2") (pinfunction "2_2") (pintype "passive"))
      (node (ref "S2") (pin "G") (pinfunction "G_G") (pintype "passive"))
      (node (ref "U4") (pin "42") (pinfunction "GH_B_42") (pintype "bidirectional"))
    )
    (net (code "47") (name "Net-(U4-GH_C)") (class "Default")
      (node (ref "R9") (pin "2") (pinfunction "2_2") (pintype "passive"))
      (node (ref "S3") (pin "G") (pinfunction "G_G") (pintype "passive"))
      (node (ref "U4") (pin "37") (pinfunction "GH_C_37") (pintype "bidirectional"))
    )
    (net (code "48") (name "Net-(U4-GL_A)") (class "Default")
      (node (ref "R10") (pin "2") (pinfunction "2_2") (pintype "passive"))
      (node (ref "S4") (pin "G") (pinfunction "G_G") (pintype "passive"))
      (node (ref "U4") (pin "45") (pinfunction "GL_A_45") (pintype "bidirectional"))
    )
    (net (code "49") (name "Net-(U4-GL_B)") (class "Default")
      (node (ref "R11") (pin "2") (pinfunction "2_2") (pintype "passive"))
      (node (ref "S5") (pin "G") (pinfunction "G_G") (pintype "passive"))
      (node (ref "U4") (pin "40") (pinfunction "GL_B_40") (pintype "bidirectional"))
    )
    (net (code "50") (name "Net-(U4-GL_C)") (class "Default")
      (node (ref "R12") (pin "2") (pinfunction "2_2") (pintype "passive"))
      (node (ref "S6") (pin "G") (pinfunction "G_G") (pintype "passive"))
      (node (ref "U4") (pin "35") (pinfunction "GL_C_35") (pintype "bidirectional"))
    )
    (net (code "51") (name "Net-(U4-GVDD)") (class "Default")
      (node (ref "C6") (pin "2") (pinfunction "2_2") (pintype "passive"))
      (node (ref "U4") (pin "13") (pinfunction "GVDD_13") (pintype "power_in"))
    )
    (net (code "52") (name "Net-(U4-PH_1)") (class "Default")
      (node (ref "C21") (pin "2") (pinfunction "2_2") (pintype "passive"))
      (node (ref "D2") (pin "C") (pinfunction "C_C") (pintype "passive"))
      (node (ref "L1") (pin "2") (pinfunction "2_2") (pintype "passive"))
      (node (ref "U4") (pin "50") (pinfunction "PH_1_50") (pintype "output"))
      (node (ref "U4") (pin "51") (pinfunction "PH_2_51") (pintype "output"))
    )
    (net (code "53") (name "Net-(U4-REF)") (class "Default")
      (node (ref "C20") (pin "2") (pinfunction "2_2") (pintype "passive"))
      (node (ref "FB3") (pin "2") (pinfunction "2_2") (pintype "passive"))
      (node (ref "U4") (pin "24") (pinfunction "REF_24") (pintype "input"))
    )
    (net (code "54") (name "Net-(U4-RT_CLK)") (class "Default")
      (node (ref "R19") (pin "1") (pinfunction "1_1") (pintype "passive"))
      (node (ref "U4") (pin "1") (pinfunction "RT_CLK_1") (pintype "input"))
    )
    (net (code "55") (name "Net-(U4-SL_B)") (class "Default")
      (node (ref "R11") (pin "1") (pinfunction "1_1") (pintype "passive"))
      (node (ref "R5") (pin "2") (pinfunction "2_2") (pintype "passive"))
      (node (ref "S5") (pin "S1") (pinfunction "S_S1") (pintype "passive"))
      (node (ref "S5") (pin "S2") (pinfunction "S_S2") (pintype "passive"))
      (node (ref "S5") (pin "S3") (pinfunction "S_S3") (pintype "passive"))
      (node (ref "U4") (pin "33") (pinfunction "SN1_33") (pintype "input"))
      (node (ref "U4") (pin "39") (pinfunction "SL_B_39") (pintype "bidirectional"))
    )
    (net (code "56") (name "Net-(U4-SL_C)") (class "Default")
      (node (ref "R12") (pin "1") (pinfunction "1_1") (pintype "passive"))
      (node (ref "R6") (pin "2") (pinfunction "2_2") (pintype "passive"))
      (node (ref "S6") (pin "S1") (pinfunction "S_S1") (pintype "passive"))
      (node (ref "S6") (pin "S2") (pinfunction "S_S2") (pintype "passive"))
      (node (ref "S6") (pin "S3") (pinfunction "S_S3") (pintype "passive"))
      (node (ref "U4") (pin "31") (pinfunction "SN2_31") (pintype "input"))
      (node (ref "U4") (pin "34") (pinfunction "SL_C_34") (pintype "bidirectional"))
    )
    (net (code "57") (name "Net-(U4-VDD_SPI)") (class "Default")
      (node (ref "C17") (pin "1") (pinfunction "1_1") (pintype "passive"))
      (node (ref "C22") (pin "1") (pinfunction "1_1") (pintype "passive"))
      (node (ref "F1") (pin "1") (pinfunction "1_1") (pintype "bidirectional"))
      (node (ref "L1") (pin "1") (pinfunction "1_1") (pintype "passive"))
      (node (ref "R21") (pin "2") (pinfunction "2_2") (pintype "passive"))
      (node (ref "U4") (pin "49") (pinfunction "VDD_SPI_49") (pintype "power_in"))
    )
    (net (code "58") (name "Net-(U4-VSENSE)") (class "Default")
      (node (ref "R21") (pin "1") (pinfunction "1_1") (pintype "passive"))
      (node (ref "R22") (pin "1") (pinfunction "1_1") (pintype "passive"))
      (node (ref "U4") (pin "3") (pinfunction "VSENSE_3") (pintype "input"))
    )
    (net (code "59") (name "PWM_A") (class "Default")
      (node (ref "IC1") (pin "31") (pinfunction "PA10_31") (pintype "bidirectional"))
      (node (ref "U4") (pin "17") (pinfunction "INH_A_17") (pintype "input"))
    )
    (net (code "60") (name "PWM_B") (class "Default")
      (node (ref "IC1") (pin "30") (pinfunction "PA9_30") (pintype "bidirectional"))
      (node (ref "U4") (pin "19") (pinfunction "INH_B_19") (pintype "input"))
    )
    (net (code "61") (name "PWM_C") (class "Default")
      (node (ref "IC1") (pin "29") (pinfunction "PA8_29") (pintype "bidirectional"))
      (node (ref "U4") (pin "21") (pinfunction "INH_C_21") (pintype "input"))
    )
    (net (code "62") (name "SWCLK") (class "Default")
      (node (ref "IC1") (pin "37") (pinfunction "PA14_37") (pintype "bidirectional"))
      (node (ref "J1") (pin "TCK") (pinfunction "TCK/SWCLK_TCK") (pintype "bidirectional"))
    )
    (net (code "63") (name "SWDIO") (class "Default")
      (node (ref "IC1") (pin "34") (pinfunction "PA13_34") (pintype "bidirectional"))
      (node (ref "J1") (pin "TMS") (pinfunction "TMS/SWDIO_TMS") (pintype "bidirectional"))
    )
    (net (code "64") (name "UART_RX") (class "Default")
      (node (ref "IC1") (pin "22") (pinfunction "PB11_22") (pintype "bidirectional"))
      (node (ref "J4") (pin "3") (pinfunction "3_3") (pintype "bidirectional"))
    )
    (net (code "65") (name "UART_TX") (class "Default")
      (node (ref "IC1") (pin "21") (pinfunction "PB10_21") (pintype "bidirectional"))
      (node (ref "J4") (pin "2") (pinfunction "2_2") (pintype "bidirectional"))
    )
    (net (code "66") (name "USB_DM") (class "Default")
      (node (ref "IC1") (pin "32") (pinfunction "PA11_32") (pintype "bidirectional"))
      (node (ref "JP3") (pin "D-") (pinfunction "D-_D-") (pintype "bidirectional"))
    )
    (net (code "67") (name "USB_DP") (class "Default")
      (node (ref "IC1") (pin "33") (pinfunction "PA12_33") (pintype "bidirectional"))
      (node (ref "JP3") (pin "D+") (pinfunction "D+_D+") (pintype "bidirectional"))
      (node (ref "R4") (pin "1") (pinfunction "1_1") (pintype "passive"))
    )
    (net (code "68") (name "V+") (class "Default")
      (node (ref "C23") (pin "1") (pinfunction "1_1") (pintype "passive"))
      (node (ref "C7") (pin "1") (pinfunction "1_1") (pintype "passive"))
      (node (ref "S1") (pin "D") (pinfunction "D_D") (pintype "passive"))
      (node (ref "S1") (pin "D_") (pinfunction "D_D_") (pintype "passive"))
      (node (ref "S2") (pin "D") (pinfunction "D_D") (pintype "passive"))
      (node (ref "S2") (pin "D_") (pinfunction "D_D_") (pintype "passive"))
      (node (ref "S3") (pin "D") (pinfunction "D_D") (pintype "passive"))
      (node (ref "S3") (pin "D_") (pinfunction "D_D_") (pintype "passive"))
      (node (ref "U4") (pin "29") (pinfunction "PVDD1_29") (pintype "power_in"))
      (node (ref "U4") (pin "53") (pinfunction "PVDD2_1_53") (pintype "power_in"))
      (node (ref "U4") (pin "54") (pinfunction "PVDD2_2_54") (pintype "power_in"))
    )
    (net (code "69") (name "V-") (class "Default")
      (node (ref "C17") (pin "2") (pinfunction "2_2") (pintype "passive"))
      (node (ref "C22") (pin "2") (pinfunction "2_2") (pintype "passive"))
      (node (ref "C23") (pin "2") (pinfunction "2_2") (pintype "passive"))
      (node (ref "C6") (pin "1") (pinfunction "1_1") (pintype "passive"))
      (node (ref "C7") (pin "2") (pinfunction "2_2") (pintype "passive"))
      (node (ref "D2") (pin "A") (pinfunction "A_A") (pintype "passive"))
      (node (ref "FB1") (pin "1") (pinfunction "1_1") (pintype "passive"))
      (node (ref "R10") (pin "1") (pinfunction "1_1") (pintype "passive"))
      (node (ref "R5") (pin "1") (pinfunction "1_1") (pintype "passive"))
      (node (ref "R6") (pin "1") (pinfunction "1_1") (pintype "passive"))
      (node (ref "S4") (pin "S1") (pinfunction "S_S1") (pintype "passive"))
      (node (ref "S4") (pin "S2") (pinfunction "S_S2") (pintype "passive"))
      (node (ref "S4") (pin "S3") (pinfunction "S_S3") (pintype "passive"))
      (node (ref "U4") (pin "30") (pinfunction "SP2_30") (pintype "input"))
      (node (ref "U4") (pin "32") (pinfunction "SP1_32") (pintype "input"))
      (node (ref "U4") (pin "44") (pinfunction "SL_A_44") (pintype "bidirectional"))
      (node (ref "U4") (pin "PWRPAD") (pinfunction "GND_PWRPAD") (pintype "power_in"))
    )
    (net (code "70") (name "unconnected-(IC1C-PA5-Pad15)") (class "Default")
      (node (ref "IC1") (pin "15") (pinfunction "PA5_15") (pintype "bidirectional"))
    )
    (net (code "71") (name "unconnected-(IC1C-PA6-Pad16)") (class "Default")
      (node (ref "IC1") (pin "16") (pinfunction "PA6_16") (pintype "bidirectional"))
    )
    (net (code "72") (name "unconnected-(IC1C-PA7-Pad17)") (class "Default")
      (node (ref "IC1") (pin "17") (pinfunction "PA7_17") (pintype "bidirectional"))
    )
    (net (code "73") (name "unconnected-(IC1E-PB0-Pad18)") (class "Default")
      (node (ref "IC1") (pin "18") (pinfunction "PB0_18") (pintype "bidirectional"))
    )
    (net (code "74") (name "unconnected-(IC1E-PB2-Pad20)") (class "Default")
      (node (ref "IC1") (pin "20") (pinfunction "PB2_20") (pintype "bidirectional"))
    )
    (net (code "75") (name "unconnected-(IC1F-PC13-Pad2)") (class "Default")
      (node (ref "IC1") (pin "2") (pinfunction "PC13_2") (pintype "bidirectional"))
    )
    (net (code "76") (name "unconnected-(IC1F-PC14-Pad3)") (class "Default")
      (node (ref "IC1") (pin "3") (pinfunction "PC14_3") (pintype "bidirectional"))
    )
    (net (code "77") (name "unconnected-(IC1F-PC15-Pad4)") (class "Default")
      (node (ref "IC1") (pin "4") (pinfunction "PC15_4") (pintype "bidirectional"))
    )
    (net (code "78") (name "unconnected-(J1-PadTDI)") (class "Default")
      (node (ref "J1") (pin "TDI") (pinfunction "TDI_TDI") (pintype "bidirectional"))
    )
    (net (code "79") (name "unconnected-(J1-TDO{slash}SWO-PadTDO)") (class "Default")
      (node (ref "J1") (pin "TDO") (pinfunction "TDO/SWO_TDO") (pintype "bidirectional"))
    )
    (net (code "80") (name "unconnected-(J4-Pad1)") (class "Default")
      (node (ref "J4") (pin "1") (pinfunction "1_1") (pintype "bidirectional"))
    )
    (net (code "81") (name "unconnected-(JP1-NTC-Pad5)") (class "Default")
      (node (ref "JP1") (pin "5") (pinfunction "NTC_5") (pintype "bidirectional"))
    )
    (net (code "82") (name "unconnected-(U4-DC_CAL-Pad12)") (class "Default")
      (node (ref "U4") (pin "12") (pinfunction "DC_CAL_12") (pintype "input"))
    )
    (net (code "83") (name "unconnected-(U4-EN_BUCK-Pad55)") (class "Default")
      (node (ref "U4") (pin "55") (pinfunction "EN_BUCK_55") (pintype "bidirectional"))
    )
    (net (code "84") (name "unconnected-(U4-PWRGD-Pad4)") (class "Default")
      (node (ref "U4") (pin "4") (pinfunction "PWRGD_4") (pintype "output"))
    )
    (net (code "85") (name "unconnected-(U4-SS_TR-Pad56)") (class "Default")
      (node (ref "U4") (pin "56") (pinfunction "SS_TR_56") (pintype "bidirectional"))
    )
    (net (code "86") (name "unconnected-(U4-~{FAULT}-Pad6)") (class "Default")
      (node (ref "U4") (pin "6") (pinfunction "~{FAULT}_6") (pintype "output"))
    )
    (net (code "87") (name "unconnected-(U4-~{OCTW}-Pad5)") (class "Default")
      (node (ref "U4") (pin "5") (pinfunction "~{OCTW}_5") (pintype "output"))
    )
    (net (code "88") (name "~{PWM_A}") (class "Default")
      (node (ref "IC1") (pin "28") (pinfunction "PB15_28") (pintype "bidirectional"))
      (node (ref "U4") (pin "18") (pinfunction "INL_A_18") (pintype "input"))
    )
    (net (code "89") (name "~{PWM_B}") (class "Default")
      (node (ref "IC1") (pin "27") (pinfunction "PB14_27") (pintype "bidirectional"))
      (node (ref "U4") (pin "20") (pinfunction "INL_B_20") (pintype "input"))
    )
    (net (code "90") (name "~{PWM_C}") (class "Default")
      (node (ref "IC1") (pin "26") (pinfunction "PB13_26") (pintype "bidirectional"))
      (node (ref "U4") (pin "22") (pinfunction "INL_C_22") (pintype "input"))
    )
    (net (code "91") (name "~{RESET}") (class "Default")
      (node (ref "C_RST") (pin "1") (pinfunction "1_1") (pintype "passive"))
      (node (ref "IC1") (pin "7") (pinfunction "NRST_7") (pintype "input"))
      (node (ref "J1") (pin "NRST") (pinfunction "NRST_NRST") (pintype "bidirectional"))
      (node (ref "U3") (pin "4") (pinfunction "POK_4") (pintype "output"))
    )
  )
)
